# main_board.net
KiCad netlist of a schematic drawn in EAGLE
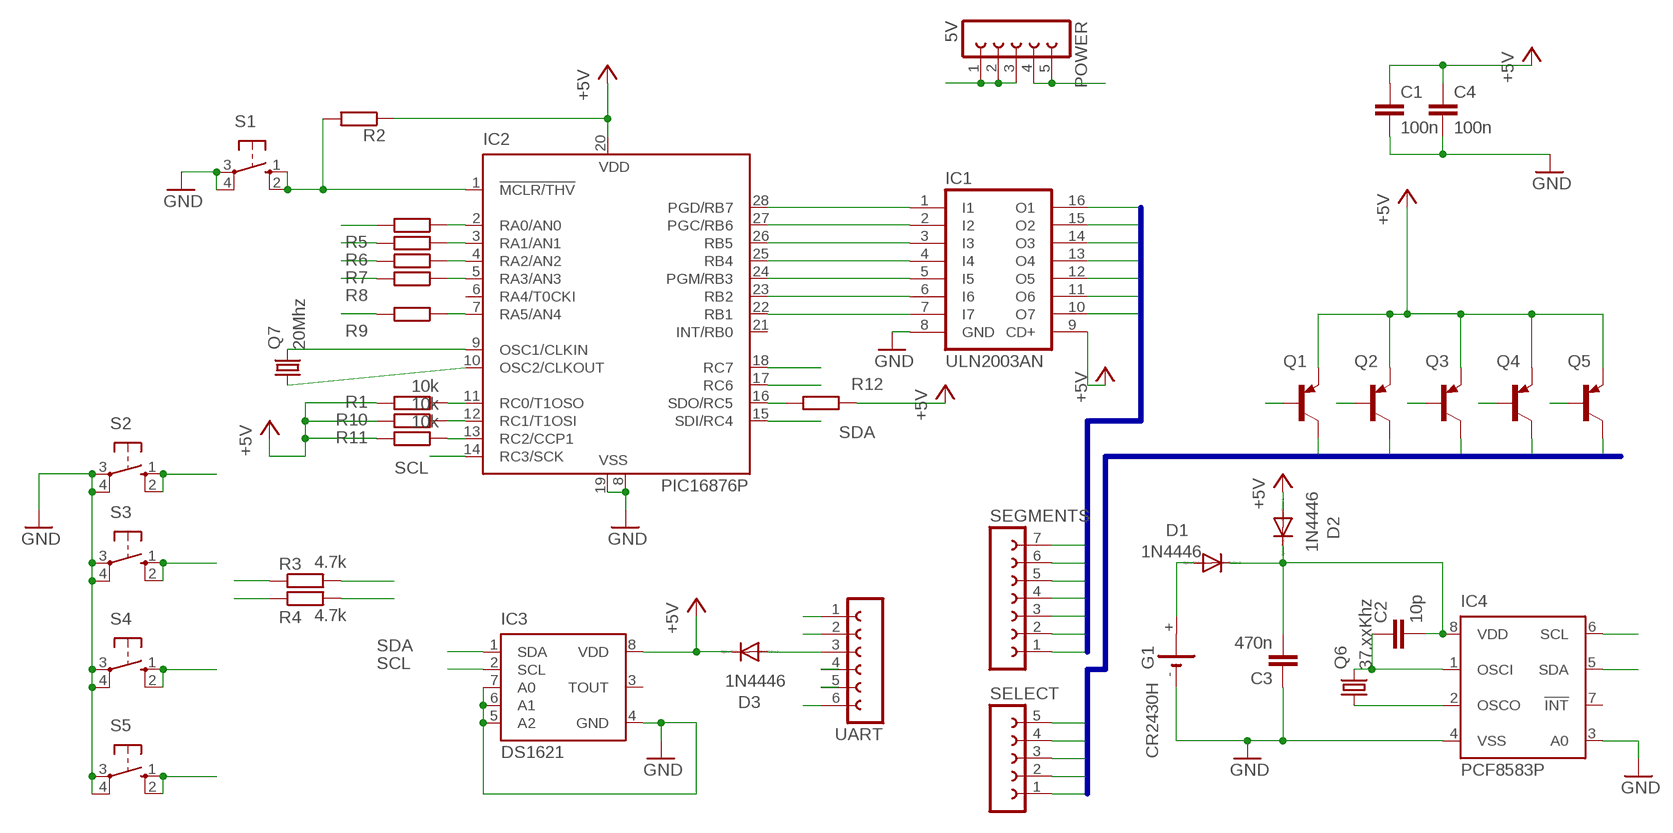
[diagram p0: schematic, sheet 1]

(export (version "E")
  (design (tool "Eeschema 10.0.6"))
  (components
    (comp (ref "C1")
      (value "100n")
      (footprint "eagle-import:C025-030X050")
      (libsource (lib "eagle-import") (part "C-EU025-030X050"))
    )
    (comp (ref "C2")
      (value "10p")
      (footprint "eagle-import:C025-030X050")
      (libsource (lib "eagle-import") (part "C-EU025-030X050"))
    )
    (comp (ref "C3")
      (value "470n")
      (footprint "eagle-import:C025-030X050")
      (libsource (lib "eagle-import") (part "C-EU025-030X050"))
    )
    (comp (ref "C4")
      (value "100n")
      (footprint "eagle-import:C025-030X050")
      (libsource (lib "eagle-import") (part "C-EU025-030X050"))
    )
    (comp (ref "D1")
      (value "1N4446")
      (footprint "eagle-import:DO35-10")
      (libsource (lib "eagle-import") (part "1N4446"))
    )
    (comp (ref "D2")
      (value "1N4446")
      (footprint "eagle-import:DO35-10")
      (libsource (lib "eagle-import") (part "1N4446"))
    )
    (comp (ref "D3")
      (value "1N4446")
      (footprint "eagle-import:DO35-10")
      (libsource (lib "eagle-import") (part "1N4446"))
    )
    (comp (ref "G1")
      (value "CR2430H")
      (footprint "eagle-import:CR2430H")
      (libsource (lib "eagle-import") (part "CR2430H"))
    )
    (comp (ref "IC1")
      (value "ULN2003AN")
      (footprint "eagle-import:DIL16")
      (libsource (lib "eagle-import") (part "ULN2003AN"))
    )
    (comp (ref "IC2")
      (value "PIC16876P")
      (footprint "eagle-import:DIL28-3")
      (libsource (lib "eagle-import") (part "PIC16876P"))
    )
    (comp (ref "IC3")
      (value "DS1621")
      (footprint "eagle-import:DIL08")
      (libsource (lib "eagle-import") (part "DS1621"))
    )
    (comp (ref "IC4")
      (value "PCF8583P")
      (footprint "eagle-import:DIL08")
      (libsource (lib "eagle-import") (part "PCF8583P"))
    )
    (comp (ref "POWER")
      (value "5V")
      (footprint "eagle-import:FE05-1")
      (libsource (lib "eagle-import") (part "FE05-1"))
    )
    (comp (ref "Q1")
      (value "BC369")
      (footprint "eagle-import:TO92-BCE")
      (libsource (lib "eagle-import") (part "BC369"))
    )
    (comp (ref "Q2")
      (value "BC369")
      (footprint "eagle-import:TO92-BCE")
      (libsource (lib "eagle-import") (part "BC369"))
    )
    (comp (ref "Q3")
      (value "BC369")
      (footprint "eagle-import:TO92-BCE")
      (libsource (lib "eagle-import") (part "BC369"))
    )
    (comp (ref "Q4")
      (value "BC369")
      (footprint "eagle-import:TO92-BCE")
      (libsource (lib "eagle-import") (part "BC369"))
    )
    (comp (ref "Q5")
      (value "BC369")
      (footprint "eagle-import:TO92-BCE")
      (libsource (lib "eagle-import") (part "BC369"))
    )
    (comp (ref "Q6")
      (value "37.xxKhz")
      (footprint "eagle-import:TC38H")
      (libsource (lib "eagle-import") (part "CRYSTALTC38H"))
    )
    (comp (ref "Q7")
      (value "20Mhz")
      (footprint "eagle-import:HC49U-V")
      (libsource (lib "eagle-import") (part "CRYSTALHC49U-V"))
    )
    (comp (ref "R1")
      (value "10k")
      (footprint "eagle-import:0204_7")
      (libsource (lib "eagle-import") (part "R-EU_0204/7"))
    )
    (comp (ref "R2")
      (value "R-EU_0204/7")
      (footprint "eagle-import:0204_7")
      (libsource (lib "eagle-import") (part "R-EU_0204/7"))
    )
    (comp (ref "R3")
      (value "4.7k")
      (footprint "eagle-import:0204_7")
      (libsource (lib "eagle-import") (part "R-EU_0204/7"))
    )
    (comp (ref "R4")
      (value "4.7k")
      (footprint "eagle-import:0204_7")
      (libsource (lib "eagle-import") (part "R-EU_0204/7"))
    )
    (comp (ref "R5")
      (value "R-EU_0204/7")
      (footprint "eagle-import:0204_7")
      (libsource (lib "eagle-import") (part "R-EU_0204/7"))
    )
    (comp (ref "R6")
      (value "R-EU_0204/7")
      (footprint "eagle-import:0204_7")
      (libsource (lib "eagle-import") (part "R-EU_0204/7"))
    )
    (comp (ref "R7")
      (value "R-EU_0204/7")
      (footprint "eagle-import:0204_7")
      (libsource (lib "eagle-import") (part "R-EU_0204/7"))
    )
    (comp (ref "R8")
      (value "R-EU_0204/7")
      (footprint "eagle-import:0204_7")
      (libsource (lib "eagle-import") (part "R-EU_0204/7"))
    )
    (comp (ref "R9")
      (value "R-EU_0204/7")
      (footprint "eagle-import:0204_7")
      (libsource (lib "eagle-import") (part "R-EU_0204/7"))
    )
    (comp (ref "R10")
      (value "10k")
      (footprint "eagle-import:0204_7")
      (libsource (lib "eagle-import") (part "R-EU_0204/7"))
    )
    (comp (ref "R11")
      (value "10k")
      (footprint "eagle-import:0204_7")
      (libsource (lib "eagle-import") (part "R-EU_0204/7"))
    )
    (comp (ref "R12")
      (value "R-EU_0204/7")
      (footprint "eagle-import:0204_7")
      (libsource (lib "eagle-import") (part "R-EU_0204/7"))
    )
    (comp (ref "S1")
      (value "10-XX")
      (footprint "eagle-import:B3F-10XX")
      (fields (field (name "MPN") "B3F-1000"))
      (libsource (lib "eagle-import") (part "10-XX"))
    )
    (comp (ref "S2")
      (value "10-XX")
      (footprint "eagle-import:B3F-10XX")
      (fields (field (name "MPN") "B3F-1000"))
      (libsource (lib "eagle-import") (part "10-XX"))
    )
    (comp (ref "S3")
      (value "10-XX")
      (footprint "eagle-import:B3F-10XX")
      (fields (field (name "MPN") "B3F-1000"))
      (libsource (lib "eagle-import") (part "10-XX"))
    )
    (comp (ref "S4")
      (value "10-XX")
      (footprint "eagle-import:B3F-10XX")
      (fields (field (name "MPN") "B3F-1000"))
      (libsource (lib "eagle-import") (part "10-XX"))
    )
    (comp (ref "S5")
      (value "10-XX")
      (footprint "eagle-import:B3F-10XX")
      (fields (field (name "MPN") "B3F-1000"))
      (libsource (lib "eagle-import") (part "10-XX"))
    )
    (comp (ref "SEGMENTS")
      (value "FE07-1")
      (footprint "eagle-import:FE07")
      (libsource (lib "eagle-import") (part "FE07-1"))
    )
    (comp (ref "SELECT")
      (value "FE05-1")
      (footprint "eagle-import:FE05-1")
      (libsource (lib "eagle-import") (part "FE05-1"))
    )
    (comp (ref "UART")
      (value "FE06-1")
      (footprint "eagle-import:FE06")
      (libsource (lib "eagle-import") (part "FE06-1"))
    )
  )
  (nets
    (net (code "1") (name "+5V") (class "Default")
      (node (ref "C1") (pin "1") (pinfunction "1_1") (pintype "passive"))
      (node (ref "C4") (pin "1") (pinfunction "1_1") (pintype "passive"))
      (node (ref "D2") (pin "A") (pinfunction "A_A") (pintype "passive"))
      (node (ref "D3") (pin "C") (pinfunction "C_C") (pintype "passive"))
      (node (ref "IC1") (pin "9") (pinfunction "CD+_9") (pintype "passive"))
      (node (ref "IC2") (pin "20") (pinfunction "VDD_20") (pintype "power_in"))
      (node (ref "IC3") (pin "8") (pinfunction "VDD_8") (pintype "power_in"))
      (node (ref "POWER") (pin "1") (pinfunction "1_1") (pintype "passive"))
      (node (ref "POWER") (pin "2") (pinfunction "2_2") (pintype "passive"))
      (node (ref "POWER") (pin "3") (pinfunction "3_3") (pintype "passive"))
      (node (ref "Q1") (pin "E") (pinfunction "E_E") (pintype "passive"))
      (node (ref "Q2") (pin "E") (pinfunction "E_E") (pintype "passive"))
      (node (ref "Q3") (pin "E") (pinfunction "E_E") (pintype "passive"))
      (node (ref "Q4") (pin "E") (pinfunction "E_E") (pintype "passive"))
      (node (ref "Q5") (pin "E") (pinfunction "E_E") (pintype "passive"))
      (node (ref "R1") (pin "2") (pinfunction "2_2") (pintype "passive"))
      (node (ref "R10") (pin "2") (pinfunction "2_2") (pintype "passive"))
      (node (ref "R11") (pin "2") (pinfunction "2_2") (pintype "passive"))
      (node (ref "R12") (pin "1") (pinfunction "1_1") (pintype "passive"))
      (node (ref "R2") (pin "1") (pinfunction "1_1") (pintype "passive"))
      (node (ref "R3") (pin "1") (pinfunction "1_1") (pintype "passive"))
      (node (ref "R4") (pin "1") (pinfunction "1_1") (pintype "passive"))
    )
    (net (code "2") (name "/J_SEG_DATA0") (class "Default")
      (node (ref "IC1") (pin "16") (pinfunction "O1_16") (pintype "open_collector"))
      (node (ref "SEGMENTS") (pin "7") (pinfunction "7_7") (pintype "passive"))
    )
    (net (code "3") (name "/J_SEG_DATA1") (class "Default")
      (node (ref "IC1") (pin "15") (pinfunction "O2_15") (pintype "open_collector"))
      (node (ref "SEGMENTS") (pin "6") (pinfunction "6_6") (pintype "passive"))
    )
    (net (code "4") (name "/J_SEG_DATA2") (class "Default")
      (node (ref "IC1") (pin "14") (pinfunction "O3_14") (pintype "open_collector"))
      (node (ref "SEGMENTS") (pin "5") (pinfunction "5_5") (pintype "passive"))
    )
    (net (code "5") (name "/J_SEG_DATA3") (class "Default")
      (node (ref "IC1") (pin "13") (pinfunction "O4_13") (pintype "open_collector"))
      (node (ref "SEGMENTS") (pin "4") (pinfunction "4_4") (pintype "passive"))
    )
    (net (code "6") (name "/J_SEG_DATA4") (class "Default")
      (node (ref "IC1") (pin "12") (pinfunction "O5_12") (pintype "open_collector"))
      (node (ref "SEGMENTS") (pin "3") (pinfunction "3_3") (pintype "passive"))
    )
    (net (code "7") (name "/J_SEG_DATA5") (class "Default")
      (node (ref "IC1") (pin "11") (pinfunction "O6_11") (pintype "open_collector"))
      (node (ref "SEGMENTS") (pin "2") (pinfunction "2_2") (pintype "passive"))
    )
    (net (code "8") (name "/J_SEG_DATA6") (class "Default")
      (node (ref "IC1") (pin "10") (pinfunction "O7_10") (pintype "open_collector"))
      (node (ref "SEGMENTS") (pin "1") (pinfunction "1_1") (pintype "passive"))
    )
    (net (code "9") (name "/J_SEG_SELECT0") (class "Default")
      (node (ref "Q1") (pin "C") (pinfunction "C_C") (pintype "passive"))
      (node (ref "SELECT") (pin "5") (pinfunction "5_5") (pintype "passive"))
    )
    (net (code "10") (name "/J_SEG_SELECT1") (class "Default")
      (node (ref "Q2") (pin "C") (pinfunction "C_C") (pintype "passive"))
      (node (ref "SELECT") (pin "4") (pinfunction "4_4") (pintype "passive"))
    )
    (net (code "11") (name "/J_SEG_SELECT2") (class "Default")
      (node (ref "Q3") (pin "C") (pinfunction "C_C") (pintype "passive"))
      (node (ref "SELECT") (pin "3") (pinfunction "3_3") (pintype "passive"))
    )
    (net (code "12") (name "/J_SEG_SELECT3") (class "Default")
      (node (ref "Q4") (pin "C") (pinfunction "C_C") (pintype "passive"))
      (node (ref "SELECT") (pin "2") (pinfunction "2_2") (pintype "passive"))
    )
    (net (code "13") (name "/J_SEG_SELECT4") (class "Default")
      (node (ref "Q5") (pin "C") (pinfunction "C_C") (pintype "passive"))
      (node (ref "SELECT") (pin "1") (pinfunction "1_1") (pintype "passive"))
    )
    (net (code "14") (name "/SCL") (class "Default")
      (node (ref "IC2") (pin "14") (pinfunction "RC3/SCK_14") (pintype "bidirectional"))
      (node (ref "IC3") (pin "2") (pinfunction "SCL_2") (pintype "input"))
      (node (ref "IC4") (pin "6") (pinfunction "SCL_6") (pintype "input"))
      (node (ref "R4") (pin "2") (pinfunction "2_2") (pintype "passive"))
    )
    (net (code "15") (name "/SDA") (class "Default")
      (node (ref "IC2") (pin "15") (pinfunction "SDI/RC4_15") (pintype "bidirectional"))
      (node (ref "IC3") (pin "1") (pinfunction "SDA_1") (pintype "bidirectional"))
      (node (ref "IC4") (pin "5") (pinfunction "SDA_5") (pintype "bidirectional"))
      (node (ref "R3") (pin "2") (pinfunction "2_2") (pintype "passive"))
    )
    (net (code "16") (name "/SEG1") (class "Default")
      (node (ref "Q1") (pin "B") (pinfunction "B_B") (pintype "passive"))
      (node (ref "R5") (pin "2") (pinfunction "2_2") (pintype "passive"))
    )
    (net (code "17") (name "/SEG2") (class "Default")
      (node (ref "Q2") (pin "B") (pinfunction "B_B") (pintype "passive"))
      (node (ref "R6") (pin "2") (pinfunction "2_2") (pintype "passive"))
    )
    (net (code "18") (name "/SEG3") (class "Default")
      (node (ref "Q3") (pin "B") (pinfunction "B_B") (pintype "passive"))
      (node (ref "R7") (pin "2") (pinfunction "2_2") (pintype "passive"))
    )
    (net (code "19") (name "/SEG4") (class "Default")
      (node (ref "Q4") (pin "B") (pinfunction "B_B") (pintype "passive"))
      (node (ref "R8") (pin "2") (pinfunction "2_2") (pintype "passive"))
    )
    (net (code "20") (name "/SEG5") (class "Default")
      (node (ref "Q5") (pin "B") (pinfunction "B_B") (pintype "passive"))
      (node (ref "R9") (pin "2") (pinfunction "2_2") (pintype "passive"))
    )
    (net (code "21") (name "/SW1") (class "Default")
      (node (ref "IC2") (pin "11") (pinfunction "RC0/T1OSO_11") (pintype "bidirectional"))
      (node (ref "R1") (pin "1") (pinfunction "1_1") (pintype "passive"))
      (node (ref "S2") (pin "1") (pinfunction "S_1") (pintype "passive"))
      (node (ref "S2") (pin "2") (pinfunction "S1_2") (pintype "passive"))
    )
    (net (code "22") (name "/SW2") (class "Default")
      (node (ref "IC2") (pin "12") (pinfunction "RC1/T1OSI_12") (pintype "bidirectional"))
      (node (ref "R10") (pin "1") (pinfunction "1_1") (pintype "passive"))
      (node (ref "S3") (pin "1") (pinfunction "S_1") (pintype "passive"))
      (node (ref "S3") (pin "2") (pinfunction "S1_2") (pintype "passive"))
    )
    (net (code "23") (name "/SW3") (class "Default")
      (node (ref "IC2") (pin "13") (pinfunction "RC2/CCP1_13") (pintype "bidirectional"))
      (node (ref "R11") (pin "1") (pinfunction "1_1") (pintype "passive"))
      (node (ref "S4") (pin "1") (pinfunction "S_1") (pintype "passive"))
      (node (ref "S4") (pin "2") (pinfunction "S1_2") (pintype "passive"))
    )
    (net (code "24") (name "/SW4") (class "Default")
      (node (ref "IC2") (pin "16") (pinfunction "SDO/RC5_16") (pintype "bidirectional"))
      (node (ref "R12") (pin "2") (pinfunction "2_2") (pintype "passive"))
      (node (ref "S5") (pin "1") (pinfunction "S_1") (pintype "passive"))
      (node (ref "S5") (pin "2") (pinfunction "S1_2") (pintype "passive"))
    )
    (net (code "25") (name "/UART_RX") (class "Default")
      (node (ref "IC2") (pin "18") (pinfunction "RC7_18") (pintype "bidirectional"))
      (node (ref "UART") (pin "4") (pinfunction "4_4") (pintype "passive"))
    )
    (net (code "26") (name "/UART_TX") (class "Default")
      (node (ref "IC2") (pin "17") (pinfunction "RC6_17") (pintype "bidirectional"))
      (node (ref "UART") (pin "5") (pinfunction "5_5") (pintype "passive"))
    )
    (net (code "27") (name "GND") (class "Default")
      (node (ref "C1") (pin "2") (pinfunction "2_2") (pintype "passive"))
      (node (ref "C3") (pin "1") (pinfunction "1_1") (pintype "passive"))
      (node (ref "C4") (pin "2") (pinfunction "2_2") (pintype "passive"))
      (node (ref "G1") (pin "-") (pinfunction "-_-") (pintype "passive"))
      (node (ref "IC1") (pin "8") (pinfunction "GND_8") (pintype "power_in"))
      (node (ref "IC2") (pin "19") (pinfunction "VSS_19") (pintype "power_in"))
      (node (ref "IC2") (pin "8") (pinfunction "VSS_8") (pintype "power_in"))
      (node (ref "IC3") (pin "4") (pinfunction "GND_4") (pintype "power_in"))
      (node (ref "IC3") (pin "5") (pinfunction "A2_5") (pintype "input"))
      (node (ref "IC3") (pin "6") (pinfunction "A1_6") (pintype "input"))
      (node (ref "IC3") (pin "7") (pinfunction "A0_7") (pintype "input"))
      (node (ref "IC4") (pin "3") (pinfunction "A0_3") (pintype "input"))
      (node (ref "IC4") (pin "4") (pinfunction "VSS_4") (pintype "power_in"))
      (node (ref "POWER") (pin "4") (pinfunction "4_4") (pintype "passive"))
      (node (ref "POWER") (pin "5") (pinfunction "5_5") (pintype "passive"))
      (node (ref "S1") (pin "3") (pinfunction "P_3") (pintype "passive"))
      (node (ref "S1") (pin "4") (pinfunction "P1_4") (pintype "passive"))
      (node (ref "S2") (pin "3") (pinfunction "P_3") (pintype "passive"))
      (node (ref "S2") (pin "4") (pinfunction "P1_4") (pintype "passive"))
      (node (ref "S3") (pin "3") (pinfunction "P_3") (pintype "passive"))
      (node (ref "S3") (pin "4") (pinfunction "P1_4") (pintype "passive"))
      (node (ref "S4") (pin "3") (pinfunction "P_3") (pintype "passive"))
      (node (ref "S4") (pin "4") (pinfunction "P1_4") (pintype "passive"))
      (node (ref "S5") (pin "3") (pinfunction "P_3") (pintype "passive"))
      (node (ref "S5") (pin "4") (pinfunction "P1_4") (pintype "passive"))
      (node (ref "UART") (pin "1") (pinfunction "1_1") (pintype "passive"))
    )
    (net (code "28") (name "Net-(D1-PadA)") (class "Default")
      (node (ref "D1") (pin "A") (pinfunction "A_A") (pintype "passive"))
      (node (ref "G1") (pin "+") (pinfunction "+_+") (pintype "passive"))
    )
    (net (code "29") (name "Net-(D3-PadA)") (class "Default")
      (node (ref "D3") (pin "A") (pinfunction "A_A") (pintype "passive"))
      (node (ref "UART") (pin "3") (pinfunction "3_3") (pintype "passive"))
    )
    (net (code "30") (name "Net-(IC1-I1)") (class "Default")
      (node (ref "IC1") (pin "1") (pinfunction "I1_1") (pintype "input"))
      (node (ref "IC2") (pin "28") (pinfunction "PGD/RB7_28") (pintype "bidirectional"))
    )
    (net (code "31") (name "Net-(IC1-I2)") (class "Default")
      (node (ref "IC1") (pin "2") (pinfunction "I2_2") (pintype "input"))
      (node (ref "IC2") (pin "27") (pinfunction "PGC/RB6_27") (pintype "bidirectional"))
    )
    (net (code "32") (name "Net-(IC1-I3)") (class "Default")
      (node (ref "IC1") (pin "3") (pinfunction "I3_3") (pintype "input"))
      (node (ref "IC2") (pin "26") (pinfunction "RB5_26") (pintype "bidirectional"))
    )
    (net (code "33") (name "Net-(IC1-I4)") (class "Default")
      (node (ref "IC1") (pin "4") (pinfunction "I4_4") (pintype "input"))
      (node (ref "IC2") (pin "25") (pinfunction "RB4_25") (pintype "bidirectional"))
    )
    (net (code "34") (name "Net-(IC1-I5)") (class "Default")
      (node (ref "IC1") (pin "5") (pinfunction "I5_5") (pintype "input"))
      (node (ref "IC2") (pin "24") (pinfunction "PGM/RB3_24") (pintype "bidirectional"))
    )
    (net (code "35") (name "Net-(IC1-I6)") (class "Default")
      (node (ref "IC1") (pin "6") (pinfunction "I6_6") (pintype "input"))
      (node (ref "IC2") (pin "23") (pinfunction "RB2_23") (pintype "bidirectional"))
    )
    (net (code "36") (name "Net-(IC1-I7)") (class "Default")
      (node (ref "IC1") (pin "7") (pinfunction "I7_7") (pintype "input"))
      (node (ref "IC2") (pin "22") (pinfunction "RB1_22") (pintype "bidirectional"))
    )
    (net (code "37") (name "Net-(IC2-OSC1{slash}CLKIN)") (class "Default")
      (node (ref "IC2") (pin "9") (pinfunction "OSC1/CLKIN_9") (pintype "input"))
      (node (ref "Q7") (pin "2") (pinfunction "2_2") (pintype "passive"))
    )
    (net (code "38") (name "Net-(IC2-OSC2{slash}CLKOUT)") (class "Default")
      (node (ref "IC2") (pin "10") (pinfunction "OSC2/CLKOUT_10") (pintype "output"))
      (node (ref "Q7") (pin "1") (pinfunction "1_1") (pintype "passive"))
    )
    (net (code "39") (name "Net-(IC2-RA0{slash}AN0)") (class "Default")
      (node (ref "IC2") (pin "2") (pinfunction "RA0/AN0_2") (pintype "bidirectional"))
      (node (ref "R5") (pin "1") (pinfunction "1_1") (pintype "passive"))
    )
    (net (code "40") (name "Net-(IC2-RA1{slash}AN1)") (class "Default")
      (node (ref "IC2") (pin "3") (pinfunction "RA1/AN1_3") (pintype "bidirectional"))
      (node (ref "R6") (pin "1") (pinfunction "1_1") (pintype "passive"))
    )
    (net (code "41") (name "Net-(IC2-RA2{slash}AN2)") (class "Default")
      (node (ref "IC2") (pin "4") (pinfunction "RA2/AN2_4") (pintype "bidirectional"))
      (node (ref "R7") (pin "1") (pinfunction "1_1") (pintype "passive"))
    )
    (net (code "42") (name "Net-(IC2-RA3{slash}AN3)") (class "Default")
      (node (ref "IC2") (pin "5") (pinfunction "RA3/AN3_5") (pintype "bidirectional"))
      (node (ref "R8") (pin "1") (pinfunction "1_1") (pintype "passive"))
    )
    (net (code "43") (name "Net-(IC2-RA5{slash}AN4)") (class "Default")
      (node (ref "IC2") (pin "7") (pinfunction "RA5/AN4_7") (pintype "bidirectional"))
      (node (ref "R9") (pin "1") (pinfunction "1_1") (pintype "passive"))
    )
    (net (code "44") (name "Net-(IC2-~{MCLR{slash}THV})") (class "Default")
      (node (ref "IC2") (pin "1") (pinfunction "~{MCLR/THV}_1") (pintype "input"))
      (node (ref "R2") (pin "2") (pinfunction "2_2") (pintype "passive"))
      (node (ref "S1") (pin "1") (pinfunction "S_1") (pintype "passive"))
      (node (ref "S1") (pin "2") (pinfunction "S1_2") (pintype "passive"))
    )
    (net (code "45") (name "Net-(IC4-OSCI)") (class "Default")
      (node (ref "C2") (pin "1") (pinfunction "1_1") (pintype "passive"))
      (node (ref "IC4") (pin "1") (pinfunction "OSCI_1") (pintype "input"))
      (node (ref "Q6") (pin "2") (pinfunction "2_2") (pintype "passive"))
    )
    (net (code "46") (name "Net-(IC4-OSCO)") (class "Default")
      (node (ref "IC4") (pin "2") (pinfunction "OSCO_2") (pintype "output"))
      (node (ref "Q6") (pin "1") (pinfunction "1_1") (pintype "passive"))
    )
    (net (code "47") (name "Net-(IC4-VDD)") (class "Default")
      (node (ref "C2") (pin "2") (pinfunction "2_2") (pintype "passive"))
      (node (ref "C3") (pin "2") (pinfunction "2_2") (pintype "passive"))
      (node (ref "D1") (pin "C") (pinfunction "C_C") (pintype "passive"))
      (node (ref "D2") (pin "C") (pinfunction "C_C") (pintype "passive"))
      (node (ref "IC4") (pin "8") (pinfunction "VDD_8") (pintype "power_in"))
    )
    (net (code "48") (name "unconnected-(G1-+-Pad+@1)") (class "Default")
      (node (ref "G1") (pin "+@1") (pinfunction "+_+@1") (pintype "passive"))
    )
    (net (code "49") (name "unconnected-(IC2-INT{slash}RB0-Pad21)") (class "Default")
      (node (ref "IC2") (pin "21") (pinfunction "INT/RB0_21") (pintype "bidirectional"))
    )
    (net (code "50") (name "unconnected-(IC2-RA4{slash}T0CKI-Pad6)") (class "Default")
      (node (ref "IC2") (pin "6") (pinfunction "RA4/T0CKI_6") (pintype "bidirectional"))
    )
    (net (code "51") (name "unconnected-(IC3-TOUT-Pad3)") (class "Default")
      (node (ref "IC3") (pin "3") (pinfunction "TOUT_3") (pintype "output"))
    )
    (net (code "52") (name "unconnected-(IC4-~{INT}-Pad7)") (class "Default")
      (node (ref "IC4") (pin "7") (pinfunction "~{INT}_7") (pintype "open_collector"))
    )
    (net (code "53") (name "unconnected-(UART-Pad2)") (class "Default")
      (node (ref "UART") (pin "2") (pinfunction "2_2") (pintype "passive"))
    )
    (net (code "54") (name "unconnected-(UART-Pad6)") (class "Default")
      (node (ref "UART") (pin "6") (pinfunction "6_6") (pintype "passive"))
    )
  )
)
